# STM32F103RBT6.net
KiCad netlist of a schematic drawn in Altium Designer
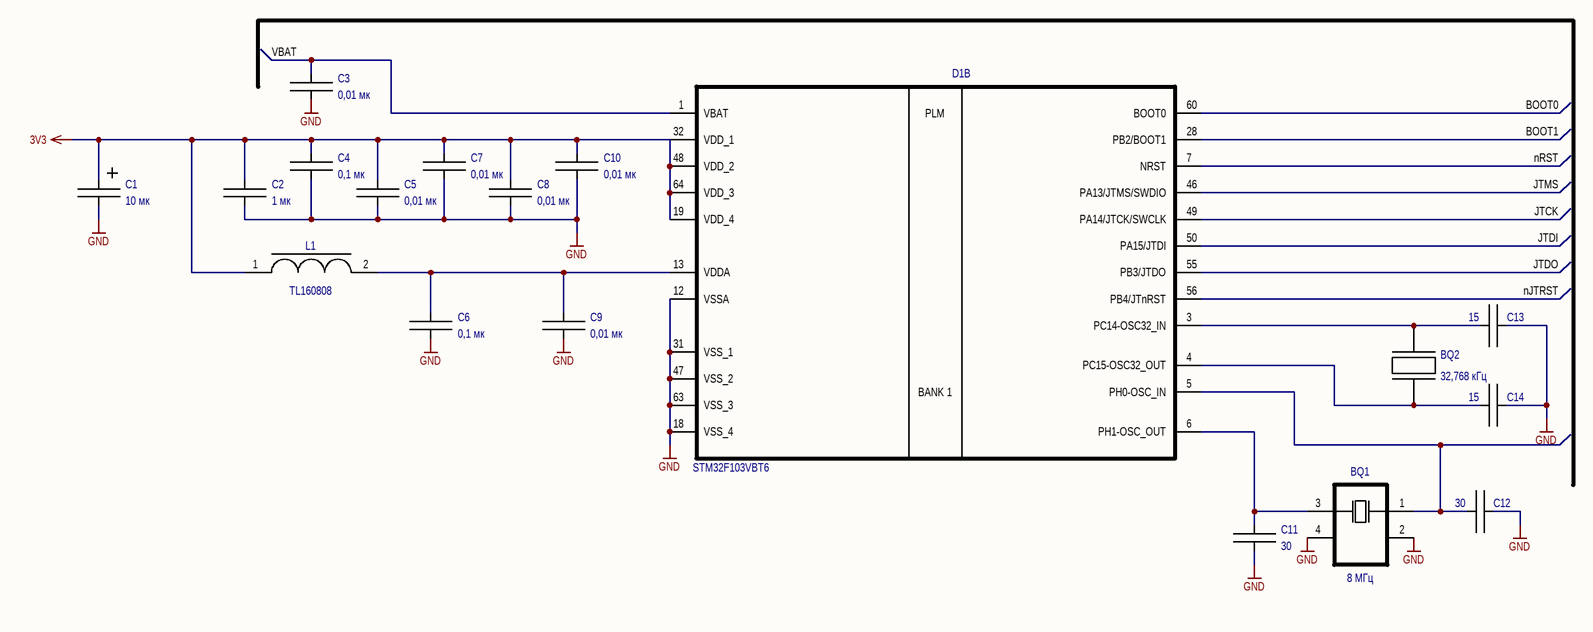
[diagram p0: Модуль STM32F103RBT6.SchDoc]

(export (version "E")
  (design (tool "Eeschema 10.0.6"))
  (components
    (comp (ref "BQ1")
      (value "8 МГц")
      (footprint "SMD3225_4P20MHZ20PF10PPM")
      (fields (field (name "PARTNUMBER") "MQ-12.000-18") (field (name "Comment") "кварцевый резонатор_1"))
      (libsource (lib "Lisaveta_SCH") (part "кварцевый резонатор_1"))
    )
    (comp (ref "BQ2")
      (value "32,768 кГц")
      (footprint "SMD3215_2P32768KHZ125PF10PPM")
      (fields (field (name "PARTNUMBER") "32,768 кГц 3215 SMD") (field (name "Comment") "3215"))
      (libsource (lib "Lisaveta") (part "кварцевый резонатор"))
    )
    (comp (ref "C1")
      (value "10 мк")
      (footprint "K53-68_3216(A)")
      (fields (field (name "Comment") "A-case"))
      (libsource (lib "Lisaveta_SCH") (part "C+"))
    )
    (comp (ref "C2")
      (value "1 мк")
      (footprint "K10-69B_2.0_1.25(0805)")
      (fields (field (name "Comment") "0805"))
      (libsource (lib "Lisaveta") (part "C"))
    )
    (comp (ref "C3")
      (value "0,01 мк")
      (footprint "K10-79_1.6_0.8(0603)")
      (fields (field (name "Comment") "0603"))
      (libsource (lib "Lisaveta") (part "C"))
    )
    (comp (ref "C4")
      (value "0,1 мк")
      (footprint "K10-79_1.6_0.8(0603)")
      (fields (field (name "Comment") "0603"))
      (libsource (lib "Lisaveta") (part "C"))
    )
    (comp (ref "C5")
      (value "0,01 мк")
      (footprint "K10-79_1.6_0.8(0603)")
      (fields (field (name "Comment") "0603"))
      (libsource (lib "Lisaveta") (part "C"))
    )
    (comp (ref "C6")
      (value "0,1 мк")
      (footprint "K10-79_1.6_0.8(0603)")
      (fields (field (name "Comment") "0603"))
      (libsource (lib "Lisaveta") (part "C"))
    )
    (comp (ref "C7")
      (value "0,01 мк")
      (footprint "K10-79_1.6_0.8(0603)")
      (fields (field (name "Comment") "0603"))
      (libsource (lib "Lisaveta") (part "C"))
    )
    (comp (ref "C8")
      (value "0,01 мк")
      (footprint "K10-79_1.6_0.8(0603)")
      (fields (field (name "Comment") "0603"))
      (libsource (lib "Lisaveta") (part "C"))
    )
    (comp (ref "C9")
      (value "0,01 мк")
      (footprint "K10-79_1.6_0.8(0603)")
      (fields (field (name "Comment") "0603"))
      (libsource (lib "Lisaveta") (part "C"))
    )
    (comp (ref "C10")
      (value "0,01 мк")
      (footprint "K10-79_1.6_0.8(0603)")
      (fields (field (name "Comment") "0603"))
      (libsource (lib "Lisaveta") (part "C"))
    )
    (comp (ref "C11")
      (value "30")
      (footprint "K10-79_1.6_0.8(0603)")
      (fields (field (name "Comment") "0603"))
      (libsource (lib "Lisaveta") (part "C"))
    )
    (comp (ref "C12")
      (value "30")
      (footprint "K10-79_1.6_0.8(0603)")
      (fields (field (name "Comment") "0603"))
      (libsource (lib "Lisaveta") (part "C"))
    )
    (comp (ref "C13")
      (value "15")
      (footprint "K10-79_1.6_0.8(0603)")
      (fields (field (name "Comment") "0603"))
      (libsource (lib "Lisaveta") (part "C"))
    )
    (comp (ref "C14")
      (value "15")
      (footprint "K10-79_1.6_0.8(0603)")
      (fields (field (name "Comment") "0603"))
      (libsource (lib "Lisaveta") (part "C"))
    )
    (comp (ref "D1")
      (value "STM32F103VBT6")
      (footprint "QFP50P1200X1200X160-64N")
      (fields (field (name "Comment") " (LQFP-48) Xilinx"))
      (libsource (lib "Lisaveta_SCH") (part "STM32F103RBT6"))
    )
    (comp (ref "L1")
      (value "TL160808")
      (footprint "742792651")
      (fields (field (name "Comment") "0603"))
      (libsource (lib "Lisaveta") (part "SH6028-5R0YLB"))
    )
  )
  (nets
    (net (code "1") (name "/BOOT0") (class "Default")
      (node (ref "D1") (pin "60") (pinfunction "BOOT0_60") (pintype "passive"))
    )
    (net (code "2") (name "/BOOT1") (class "Default")
      (node (ref "D1") (pin "28") (pinfunction "PB2/BOOT1_28") (pintype "passive"))
    )
    (net (code "3") (name "/JTCK") (class "Default")
      (node (ref "D1") (pin "49") (pinfunction "PA14/JTCK/SWCLK_49") (pintype "passive"))
    )
    (net (code "4") (name "/JTDI") (class "Default")
      (node (ref "D1") (pin "50") (pinfunction "PA15/JTDI_50") (pintype "passive"))
    )
    (net (code "5") (name "/JTDO") (class "Default")
      (node (ref "D1") (pin "55") (pinfunction "PB3/JTDO_55") (pintype "passive"))
    )
    (net (code "6") (name "/JTMS") (class "Default")
      (node (ref "D1") (pin "46") (pinfunction "PA13/JTMS/SWDIO_46") (pintype "passive"))
    )
    (net (code "7") (name "/VBAT") (class "Default")
      (node (ref "C3") (pin "2") (pinfunction "2_2") (pintype "passive"))
      (node (ref "D1") (pin "1") (pinfunction "VBAT_1") (pintype "passive"))
    )
    (net (code "8") (name "/nJTRST") (class "Default")
      (node (ref "D1") (pin "56") (pinfunction "PB4/JTnRST_56") (pintype "passive"))
    )
    (net (code "9") (name "/nRST") (class "Default")
      (node (ref "D1") (pin "7") (pinfunction "NRST_7") (pintype "passive"))
    )
    (net (code "10") (name "3V3") (class "Default")
      (node (ref "C1") (pin "1") (pinfunction "1_1") (pintype "passive"))
      (node (ref "C10") (pin "2") (pinfunction "2_2") (pintype "passive"))
      (node (ref "C2") (pin "2") (pinfunction "2_2") (pintype "passive"))
      (node (ref "C4") (pin "2") (pinfunction "2_2") (pintype "passive"))
      (node (ref "C5") (pin "2") (pinfunction "2_2") (pintype "passive"))
      (node (ref "C7") (pin "2") (pinfunction "2_2") (pintype "passive"))
      (node (ref "C8") (pin "2") (pinfunction "2_2") (pintype "passive"))
      (node (ref "D1") (pin "19") (pinfunction "VDD_4_19") (pintype "passive"))
      (node (ref "D1") (pin "32") (pinfunction "VDD_1_32") (pintype "passive"))
      (node (ref "D1") (pin "48") (pinfunction "VDD_2_48") (pintype "passive"))
      (node (ref "D1") (pin "64") (pinfunction "VDD_3_64") (pintype "passive"))
      (node (ref "L1") (pin "1") (pinfunction "1_1") (pintype "passive"))
    )
    (net (code "11") (name "GND") (class "Default")
      (node (ref "BQ1") (pin "2") (pinfunction "GND_2") (pintype "passive"))
      (node (ref "BQ1") (pin "4") (pinfunction "GND_4") (pintype "passive"))
      (node (ref "C1") (pin "2") (pinfunction "2_2") (pintype "passive"))
      (node (ref "C10") (pin "1") (pinfunction "1_1") (pintype "passive"))
      (node (ref "C11") (pin "1") (pinfunction "1_1") (pintype "passive"))
      (node (ref "C12") (pin "1") (pinfunction "1_1") (pintype "passive"))
      (node (ref "C13") (pin "1") (pinfunction "1_1") (pintype "passive"))
      (node (ref "C14") (pin "1") (pinfunction "1_1") (pintype "passive"))
      (node (ref "C2") (pin "1") (pinfunction "1_1") (pintype "passive"))
      (node (ref "C3") (pin "1") (pinfunction "1_1") (pintype "passive"))
      (node (ref "C4") (pin "1") (pinfunction "1_1") (pintype "passive"))
      (node (ref "C5") (pin "1") (pinfunction "1_1") (pintype "passive"))
      (node (ref "C6") (pin "1") (pinfunction "1_1") (pintype "passive"))
      (node (ref "C7") (pin "1") (pinfunction "1_1") (pintype "passive"))
      (node (ref "C8") (pin "1") (pinfunction "1_1") (pintype "passive"))
      (node (ref "C9") (pin "1") (pinfunction "1_1") (pintype "passive"))
      (node (ref "D1") (pin "12") (pinfunction "VSSA_12") (pintype "passive"))
      (node (ref "D1") (pin "18") (pinfunction "VSS_4_18") (pintype "passive"))
      (node (ref "D1") (pin "31") (pinfunction "VSS_1_31") (pintype "passive"))
      (node (ref "D1") (pin "47") (pinfunction "VSS_2_47") (pintype "passive"))
      (node (ref "D1") (pin "63") (pinfunction "VSS_3_63") (pintype "passive"))
    )
    (net (code "12") (name "Net-(BQ2-GND)") (class "Default")
      (node (ref "BQ2") (pin "2") (pinfunction "GND_2") (pintype "passive"))
      (node (ref "C14") (pin "2") (pinfunction "2_2") (pintype "passive"))
      (node (ref "D1") (pin "4") (pinfunction "PC15-OSC32_OUT_4") (pintype "passive"))
    )
    (net (code "13") (name "Net-(BQ2-IN)") (class "Default")
      (node (ref "BQ2") (pin "1") (pinfunction "IN_1") (pintype "passive"))
      (node (ref "C13") (pin "2") (pinfunction "2_2") (pintype "passive"))
      (node (ref "D1") (pin "3") (pinfunction "PC14-OSC32_IN_3") (pintype "passive"))
    )
    (net (code "14") (name "Net-(D1B-PH0-OSC_IN)") (class "Default")
      (node (ref "BQ1") (pin "1") (pinfunction "1_1") (pintype "passive"))
      (node (ref "C12") (pin "2") (pinfunction "2_2") (pintype "passive"))
      (node (ref "D1") (pin "5") (pinfunction "PH0-OSC_IN_5") (pintype "passive"))
    )
    (net (code "15") (name "Net-(D1B-PH1-OSC_OUT)") (class "Default")
      (node (ref "BQ1") (pin "3") (pinfunction "3_3") (pintype "passive"))
      (node (ref "C11") (pin "2") (pinfunction "2_2") (pintype "passive"))
      (node (ref "D1") (pin "6") (pinfunction "PH1-OSC_OUT_6") (pintype "passive"))
    )
    (net (code "16") (name "Net-(D1B-VDDA)") (class "Default")
      (node (ref "C6") (pin "2") (pinfunction "2_2") (pintype "passive"))
      (node (ref "C9") (pin "2") (pinfunction "2_2") (pintype "passive"))
      (node (ref "D1") (pin "13") (pinfunction "VDDA_13") (pintype "passive"))
      (node (ref "L1") (pin "2") (pinfunction "2_2") (pintype "passive"))
    )
  )
)
